# routeur3a.net
KiCad netlist of a schematic drawn in EAGLE
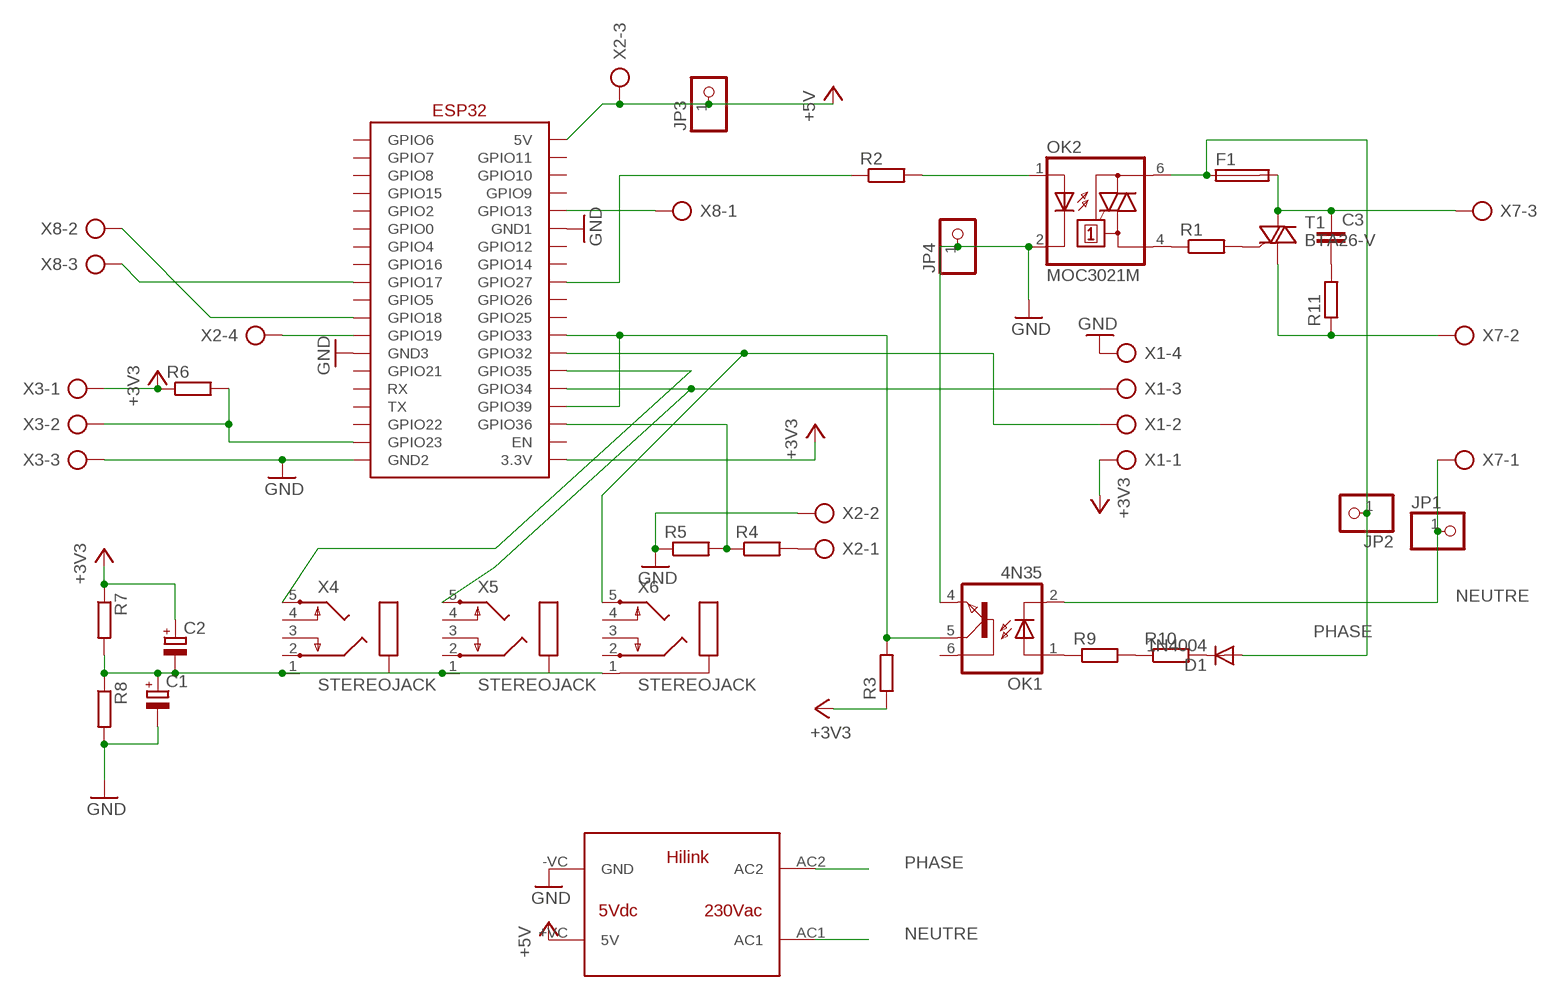
[diagram p0: schematic, sheet 1]

(export (version "E")
  (design (tool "Eeschema 10.0.6"))
  (components
    (comp (ref "C1")
      (value "CPOL-EUE5-8.5")
      (footprint "eagle-import:E5-8,5")
      (libsource (lib "eagle-import") (part "CPOL-EUE5-8.5"))
    )
    (comp (ref "C2")
      (value "CPOL-EUE5-8.5")
      (footprint "eagle-import:E5-8,5")
      (libsource (lib "eagle-import") (part "CPOL-EUE5-8.5"))
    )
    (comp (ref "C3")
      (value "C-EU150-072X183")
      (footprint "eagle-import:C150-072X183")
      (libsource (lib "eagle-import") (part "C-EU150-072X183"))
    )
    (comp (ref "D1")
      (value "1N4004")
      (footprint "eagle-import:DO41-10")
      (libsource (lib "eagle-import") (part "1N4004"))
    )
    (comp (ref "F1")
      (value "19560")
      (footprint "eagle-import:19560")
      (fields (field (name "MPN") "56000001009"))
      (libsource (lib "eagle-import") (part "19560"))
    )
    (comp (ref "JP1")
      (value "PINHD-1X1")
      (footprint "eagle-import:1X01")
      (libsource (lib "eagle-import") (part "PINHD-1X1"))
    )
    (comp (ref "JP2")
      (value "PINHD-1X1")
      (footprint "eagle-import:1X01")
      (libsource (lib "eagle-import") (part "PINHD-1X1"))
    )
    (comp (ref "JP3")
      (value "PINHD-1X1")
      (footprint "eagle-import:1X01")
      (libsource (lib "eagle-import") (part "PINHD-1X1"))
    )
    (comp (ref "JP4")
      (value "PINHD-1X1")
      (footprint "eagle-import:1X01")
      (libsource (lib "eagle-import") (part "PINHD-1X1"))
    )
    (comp (ref "OK1")
      (value "4N35")
      (footprint "eagle-import:DIL06")
      (fields (field (name "MF") "FAIRCHILD SEMICONDUCTOR"))
      (libsource (lib "eagle-import") (part "4N35"))
    )
    (comp (ref "OK2")
      (value "MOC3021M")
      (footprint "eagle-import:DIL06")
      (fields (field (name "MF") "FAIRCHILD SEMICONDUCTOR") (field (name "MPN") "MOC3021-M"))
      (libsource (lib "eagle-import") (part "MOC30M21"))
    )
    (comp (ref "R1")
      (value "R-EU_0207/10")
      (footprint "eagle-import:0207_10")
      (libsource (lib "eagle-import") (part "R-EU_0207/10"))
    )
    (comp (ref "R2")
      (value "R-EU_R1206")
      (footprint "eagle-import:R1206")
      (libsource (lib "eagle-import") (part "resistor_R-EU_R1206"))
    )
    (comp (ref "R3")
      (value "R-EU_R1206")
      (footprint "eagle-import:R1206")
      (libsource (lib "eagle-import") (part "resistor_R-EU_R1206"))
    )
    (comp (ref "R4")
      (value "R-EU_R1206")
      (footprint "eagle-import:R1206")
      (libsource (lib "eagle-import") (part "resistor_R-EU_R1206"))
    )
    (comp (ref "R5")
      (value "R-EU_R1206")
      (footprint "eagle-import:R1206")
      (libsource (lib "eagle-import") (part "resistor_R-EU_R1206"))
    )
    (comp (ref "R6")
      (value "R-EU_R1206")
      (footprint "eagle-import:R1206")
      (libsource (lib "eagle-import") (part "resistor_R-EU_R1206"))
    )
    (comp (ref "R7")
      (value "R-EU_R1206")
      (footprint "eagle-import:R1206")
      (libsource (lib "eagle-import") (part "resistor_R-EU_R1206"))
    )
    (comp (ref "R8")
      (value "R-EU_R1206")
      (footprint "eagle-import:R1206")
      (libsource (lib "eagle-import") (part "resistor_R-EU_R1206"))
    )
    (comp (ref "R9")
      (value "R-EU_0207/10")
      (footprint "eagle-import:0207_10")
      (libsource (lib "eagle-import") (part "R-EU_0207/10"))
    )
    (comp (ref "R10")
      (value "R-EU_0207/10")
      (footprint "eagle-import:0207_10")
      (libsource (lib "eagle-import") (part "R-EU_0207/10"))
    )
    (comp (ref "R11")
      (value "R-EU_0817/22")
      (footprint "eagle-import:P0817_22")
      (libsource (lib "eagle-import") (part "resistor_R-EU_0817/22"))
    )
    (comp (ref "T1")
      (value "BTA26-V")
      (footprint "eagle-import:TOP3S-1")
      (libsource (lib "eagle-import") (part "BTA26-V"))
    )
    (comp (ref "U$1")
      (value "WEMOSD1ESP32")
      (footprint "eagle-import:WEMOS-D1-MINI")
      (libsource (lib "eagle-import") (part "WEMOSD1ESP32"))
    )
    (comp (ref "U$2")
      (value "HILINK")
      (footprint "eagle-import:HILINK")
      (libsource (lib "eagle-import") (part "HILINK"))
    )
    (comp (ref "X1")
      (value "AK500/4")
      (footprint "eagle-import:AK500_4")
      (libsource (lib "eagle-import") (part "AK500/4"))
    )
    (comp (ref "X2")
      (value "AK500/4")
      (footprint "eagle-import:AK500_4")
      (libsource (lib "eagle-import") (part "AK500/4"))
    )
    (comp (ref "X3")
      (value "AK500/3")
      (footprint "eagle-import:AK500_3")
      (libsource (lib "eagle-import") (part "AK500/3"))
    )
    (comp (ref "X4")
      (value "STEREOJACK")
      (footprint "eagle-import:STX3100")
      (libsource (lib "eagle-import") (part "STEREOJACK"))
    )
    (comp (ref "X5")
      (value "STEREOJACK")
      (footprint "eagle-import:STX3100")
      (libsource (lib "eagle-import") (part "STEREOJACK"))
    )
    (comp (ref "X6")
      (value "STEREOJACK")
      (footprint "eagle-import:STX3100")
      (libsource (lib "eagle-import") (part "STEREOJACK"))
    )
    (comp (ref "X7")
      (value "AK500/3")
      (footprint "eagle-import:AK500_3")
      (libsource (lib "eagle-import") (part "AK500/3"))
    )
    (comp (ref "X8")
      (value "AK500/3")
      (footprint "eagle-import:AK500_3")
      (libsource (lib "eagle-import") (part "AK500/3"))
    )
  )
  (nets
    (net (code "1") (name "+3V3") (class "Default")
      (node (ref "C2") (pin "+") (pinfunction "+_+") (pintype "passive"))
      (node (ref "R3") (pin "1") (pinfunction "1_1") (pintype "passive"))
      (node (ref "R6") (pin "1") (pinfunction "1_1") (pintype "passive"))
      (node (ref "R7") (pin "1") (pinfunction "1_1") (pintype "passive"))
      (node (ref "U$1") (pin "3V3") (pinfunction "3.3V_3V3") (pintype "bidirectional"))
      (node (ref "X1") (pin "1") (pinfunction "KL_1") (pintype "passive"))
      (node (ref "X3") (pin "1") (pinfunction "KL_1") (pintype "passive"))
    )
    (net (code "2") (name "+5V") (class "Default")
      (node (ref "JP3") (pin "1") (pinfunction "1_1") (pintype "passive"))
      (node (ref "U$1") (pin "VCC") (pinfunction "5V_VCC") (pintype "bidirectional"))
      (node (ref "U$2") (pin "+VC") (pinfunction "5V_+VC") (pintype "bidirectional"))
      (node (ref "X2") (pin "3") (pinfunction "KL_3") (pintype "passive"))
    )
    (net (code "3") (name "/NEUTRE") (class "Default")
      (node (ref "JP1") (pin "1") (pinfunction "1_1") (pintype "passive"))
      (node (ref "OK1") (pin "2") (pinfunction "C_2") (pintype "passive"))
      (node (ref "U$2") (pin "AC1") (pinfunction "AC1_AC1") (pintype "bidirectional"))
      (node (ref "X7") (pin "1") (pinfunction "KL_1") (pintype "passive"))
    )
    (net (code "4") (name "/PHASE") (class "Default")
      (node (ref "D1") (pin "A") (pinfunction "A_A") (pintype "passive"))
      (node (ref "F1") (pin "1") (pinfunction "1_1") (pintype "passive"))
      (node (ref "JP2") (pin "1") (pinfunction "1_1") (pintype "passive"))
      (node (ref "OK2") (pin "6") (pinfunction "A2_6") (pintype "passive"))
      (node (ref "U$2") (pin "AC2") (pinfunction "AC2_AC2") (pintype "bidirectional"))
    )
    (net (code "5") (name "GND") (class "Default")
      (node (ref "C1") (pin "-") (pinfunction "-_-") (pintype "passive"))
      (node (ref "JP4") (pin "1") (pinfunction "1_1") (pintype "passive"))
      (node (ref "OK1") (pin "4") (pinfunction "EMI_4") (pintype "passive"))
      (node (ref "OK2") (pin "2") (pinfunction "C_2") (pintype "passive"))
      (node (ref "R5") (pin "1") (pinfunction "1_1") (pintype "passive"))
      (node (ref "R8") (pin "2") (pinfunction "2_2") (pintype "passive"))
      (node (ref "U$1") (pin "GND") (pinfunction "GND1_GND") (pintype "bidirectional"))
      (node (ref "U$1") (pin "GND2") (pinfunction "GND2_GND2") (pintype "bidirectional"))
      (node (ref "U$1") (pin "GND3") (pinfunction "GND3_GND3") (pintype "bidirectional"))
      (node (ref "U$2") (pin "-VC") (pinfunction "GND_-VC") (pintype "bidirectional"))
      (node (ref "X1") (pin "4") (pinfunction "KL_4") (pintype "passive"))
      (node (ref "X2") (pin "2") (pinfunction "KL_2") (pintype "passive"))
      (node (ref "X3") (pin "3") (pinfunction "KL_3") (pintype "passive"))
    )
    (net (code "6") (name "Net-(C1-Pad+)") (class "Default")
      (node (ref "C1") (pin "+") (pinfunction "+_+") (pintype "passive"))
      (node (ref "C2") (pin "-") (pinfunction "-_-") (pintype "passive"))
      (node (ref "R7") (pin "2") (pinfunction "2_2") (pintype "passive"))
      (node (ref "R8") (pin "1") (pinfunction "1_1") (pintype "passive"))
      (node (ref "X4") (pin "1") (pinfunction "1_1") (pintype "passive"))
      (node (ref "X5") (pin "1") (pinfunction "1_1") (pintype "passive"))
      (node (ref "X6") (pin "1") (pinfunction "1_1") (pintype "passive"))
    )
    (net (code "7") (name "Net-(C3-Pad2)") (class "Default")
      (node (ref "C3") (pin "2") (pinfunction "2_2") (pintype "passive"))
      (node (ref "R11") (pin "2") (pinfunction "2_2") (pintype "passive"))
    )
    (net (code "8") (name "Net-(D1-PadC)") (class "Default")
      (node (ref "D1") (pin "C") (pinfunction "C_C") (pintype "passive"))
      (node (ref "R10") (pin "2") (pinfunction "2_2") (pintype "passive"))
    )
    (net (code "9") (name "Net-(OK1-A)") (class "Default")
      (node (ref "OK1") (pin "1") (pinfunction "A_1") (pintype "passive"))
      (node (ref "R9") (pin "1") (pinfunction "1_1") (pintype "passive"))
    )
    (net (code "10") (name "Net-(OK1-COL)") (class "Default")
      (node (ref "OK1") (pin "5") (pinfunction "COL_5") (pintype "passive"))
      (node (ref "R3") (pin "2") (pinfunction "2_2") (pintype "passive"))
      (node (ref "U$1") (pin "33") (pinfunction "GPIO33_33") (pintype "bidirectional"))
      (node (ref "U$1") (pin "SUN") (pinfunction "GPIO39_SUN") (pintype "bidirectional"))
    )
    (net (code "11") (name "Net-(OK2-A)") (class "Default")
      (node (ref "OK2") (pin "1") (pinfunction "A_1") (pintype "passive"))
      (node (ref "R2") (pin "2") (pinfunction "2_2") (pintype "passive"))
    )
    (net (code "12") (name "Net-(OK2-A1)") (class "Default")
      (node (ref "OK2") (pin "4") (pinfunction "A1_4") (pintype "passive"))
      (node (ref "R1") (pin "1") (pinfunction "1_1") (pintype "passive"))
    )
    (net (code "13") (name "Net-(R1-Pad2)") (class "Default")
      (node (ref "R1") (pin "2") (pinfunction "2_2") (pintype "passive"))
      (node (ref "T1") (pin "G") (pinfunction "G_G") (pintype "passive"))
    )
    (net (code "14") (name "Net-(R10-Pad1)") (class "Default")
      (node (ref "R10") (pin "1") (pinfunction "1_1") (pintype "passive"))
      (node (ref "R9") (pin "2") (pinfunction "2_2") (pintype "passive"))
    )
    (net (code "15") (name "Net-(U$1-GPIO13)") (class "Default")
      (node (ref "U$1") (pin "TCK") (pinfunction "GPIO13_TCK") (pintype "bidirectional"))
      (node (ref "X8") (pin "1") (pinfunction "KL_1") (pintype "passive"))
    )
    (net (code "16") (name "Net-(U$1-GPIO17)") (class "Default")
      (node (ref "U$1") (pin "17") (pinfunction "GPIO17_17") (pintype "bidirectional"))
      (node (ref "X8") (pin "3") (pinfunction "KL_3") (pintype "passive"))
    )
    (net (code "17") (name "Net-(U$1-GPIO18)") (class "Default")
      (node (ref "U$1") (pin "18") (pinfunction "GPIO18_18") (pintype "bidirectional"))
      (node (ref "X8") (pin "2") (pinfunction "KL_2") (pintype "passive"))
    )
    (net (code "18") (name "Net-(U$1-GPIO19)") (class "Default")
      (node (ref "U$1") (pin "19") (pinfunction "GPIO19_19") (pintype "bidirectional"))
      (node (ref "X2") (pin "4") (pinfunction "KL_4") (pintype "passive"))
    )
    (net (code "19") (name "Net-(U$1-GPIO23)") (class "Default")
      (node (ref "R6") (pin "2") (pinfunction "2_2") (pintype "passive"))
      (node (ref "U$1") (pin "23") (pinfunction "GPIO23_23") (pintype "bidirectional"))
      (node (ref "X3") (pin "2") (pinfunction "KL_2") (pintype "passive"))
    )
    (net (code "20") (name "Net-(U$1-GPIO27)") (class "Default")
      (node (ref "R2") (pin "1") (pinfunction "1_1") (pintype "passive"))
      (node (ref "U$1") (pin "27") (pinfunction "GPIO27_27") (pintype "bidirectional"))
    )
    (net (code "21") (name "Net-(U$1-GPIO32)") (class "Default")
      (node (ref "U$1") (pin "32") (pinfunction "GPIO32_32") (pintype "bidirectional"))
      (node (ref "X1") (pin "2") (pinfunction "KL_2") (pintype "passive"))
      (node (ref "X6") (pin "5") (pinfunction "5_5") (pintype "passive"))
    )
    (net (code "22") (name "Net-(U$1-GPIO34)") (class "Default")
      (node (ref "U$1") (pin "34") (pinfunction "GPIO34_34") (pintype "bidirectional"))
      (node (ref "X1") (pin "3") (pinfunction "KL_3") (pintype "passive"))
      (node (ref "X5") (pin "5") (pinfunction "5_5") (pintype "passive"))
    )
    (net (code "23") (name "Net-(U$1-GPIO35)") (class "Default")
      (node (ref "U$1") (pin "35") (pinfunction "GPIO35_35") (pintype "bidirectional"))
      (node (ref "X4") (pin "5") (pinfunction "5_5") (pintype "passive"))
    )
    (net (code "24") (name "Net-(U$1-GPIO36)") (class "Default")
      (node (ref "R4") (pin "1") (pinfunction "1_1") (pintype "passive"))
      (node (ref "R5") (pin "2") (pinfunction "2_2") (pintype "passive"))
      (node (ref "U$1") (pin "SVP") (pinfunction "GPIO36_SVP") (pintype "bidirectional"))
    )
    (net (code "25") (name "Net-(X2A-KL)") (class "Default")
      (node (ref "R4") (pin "2") (pinfunction "2_2") (pintype "passive"))
      (node (ref "X2") (pin "1") (pinfunction "KL_1") (pintype "passive"))
    )
    (net (code "26") (name "Net-(X7B-KL)") (class "Default")
      (node (ref "R11") (pin "1") (pinfunction "1_1") (pintype "passive"))
      (node (ref "T1") (pin "A1") (pinfunction "A1_A1") (pintype "passive"))
      (node (ref "X7") (pin "2") (pinfunction "KL_2") (pintype "passive"))
    )
    (net (code "27") (name "Net-(X7C-KL)") (class "Default")
      (node (ref "C3") (pin "1") (pinfunction "1_1") (pintype "passive"))
      (node (ref "F1") (pin "2") (pinfunction "2_2") (pintype "passive"))
      (node (ref "T1") (pin "A2") (pinfunction "A2_A2") (pintype "passive"))
      (node (ref "X7") (pin "3") (pinfunction "KL_3") (pintype "passive"))
    )
    (net (code "28") (name "unconnected-(OK1-BAS-Pad6)") (class "Default")
      (node (ref "OK1") (pin "6") (pinfunction "BAS_6") (pintype "passive"))
    )
    (net (code "29") (name "unconnected-(U$1-EN-PadRST)") (class "Default")
      (node (ref "U$1") (pin "RST") (pinfunction "EN_RST") (pintype "bidirectional"))
    )
    (net (code "30") (name "unconnected-(U$1-GPIO0-Pad00)") (class "Default")
      (node (ref "U$1") (pin "00") (pinfunction "GPIO0_00") (pintype "bidirectional"))
    )
    (net (code "31") (name "unconnected-(U$1-GPIO2-Pad02)") (class "Default")
      (node (ref "U$1") (pin "02") (pinfunction "GPIO2_02") (pintype "bidirectional"))
    )
    (net (code "32") (name "unconnected-(U$1-GPIO4-Pad04)") (class "Default")
      (node (ref "U$1") (pin "04") (pinfunction "GPIO4_04") (pintype "bidirectional"))
    )
    (net (code "33") (name "unconnected-(U$1-GPIO5-Pad05)") (class "Default")
      (node (ref "U$1") (pin "05") (pinfunction "GPIO5_05") (pintype "bidirectional"))
    )
    (net (code "34") (name "unconnected-(U$1-GPIO6-PadCLK)") (class "Default")
      (node (ref "U$1") (pin "CLK") (pinfunction "GPIO6_CLK") (pintype "bidirectional"))
    )
    (net (code "35") (name "unconnected-(U$1-GPIO7-PadSDO)") (class "Default")
      (node (ref "U$1") (pin "SDO") (pinfunction "GPIO7_SDO") (pintype "bidirectional"))
    )
    (net (code "36") (name "unconnected-(U$1-GPIO8-PadSD1)") (class "Default")
      (node (ref "U$1") (pin "SD1") (pinfunction "GPIO8_SD1") (pintype "bidirectional"))
    )
    (net (code "37") (name "unconnected-(U$1-GPIO9-PadSD2)") (class "Default")
      (node (ref "U$1") (pin "SD2") (pinfunction "GPIO9_SD2") (pintype "bidirectional"))
    )
    (net (code "38") (name "unconnected-(U$1-GPIO10-PadSD3)") (class "Default")
      (node (ref "U$1") (pin "SD3") (pinfunction "GPIO10_SD3") (pintype "bidirectional"))
    )
    (net (code "39") (name "unconnected-(U$1-GPIO11-PadCMD)") (class "Default")
      (node (ref "U$1") (pin "CMD") (pinfunction "GPIO11_CMD") (pintype "bidirectional"))
    )
    (net (code "40") (name "unconnected-(U$1-GPIO12-PadTDI)") (class "Default")
      (node (ref "U$1") (pin "TDI") (pinfunction "GPIO12_TDI") (pintype "bidirectional"))
    )
    (net (code "41") (name "unconnected-(U$1-GPIO14-PadTMS)") (class "Default")
      (node (ref "U$1") (pin "TMS") (pinfunction "GPIO14_TMS") (pintype "bidirectional"))
    )
    (net (code "42") (name "unconnected-(U$1-GPIO15-PadTDO)") (class "Default")
      (node (ref "U$1") (pin "TDO") (pinfunction "GPIO15_TDO") (pintype "bidirectional"))
    )
    (net (code "43") (name "unconnected-(U$1-GPIO16-Pad16)") (class "Default")
      (node (ref "U$1") (pin "16") (pinfunction "GPIO16_16") (pintype "bidirectional"))
    )
    (net (code "44") (name "unconnected-(U$1-GPIO21-Pad21)") (class "Default")
      (node (ref "U$1") (pin "21") (pinfunction "GPIO21_21") (pintype "bidirectional"))
    )
    (net (code "45") (name "unconnected-(U$1-GPIO22-Pad22)") (class "Default")
      (node (ref "U$1") (pin "22") (pinfunction "GPIO22_22") (pintype "bidirectional"))
    )
    (net (code "46") (name "unconnected-(U$1-GPIO25-Pad25)") (class "Default")
      (node (ref "U$1") (pin "25") (pinfunction "GPIO25_25") (pintype "bidirectional"))
    )
    (net (code "47") (name "unconnected-(U$1-GPIO26-Pad26)") (class "Default")
      (node (ref "U$1") (pin "26") (pinfunction "GPIO26_26") (pintype "bidirectional"))
    )
    (net (code "48") (name "unconnected-(U$1-RX-PadRXD)") (class "Default")
      (node (ref "U$1") (pin "RXD") (pinfunction "RX_RXD") (pintype "bidirectional"))
    )
    (net (code "49") (name "unconnected-(U$1-TX-PadTXD)") (class "Default")
      (node (ref "U$1") (pin "TXD") (pinfunction "TX_TXD") (pintype "bidirectional"))
    )
    (net (code "50") (name "unconnected-(X4-Pad2)") (class "Default")
      (node (ref "X4") (pin "2") (pinfunction "2_2") (pintype "passive"))
    )
    (net (code "51") (name "unconnected-(X4-Pad3)") (class "Default")
      (node (ref "X4") (pin "3") (pinfunction "3_3") (pintype "passive"))
    )
    (net (code "52") (name "unconnected-(X4-Pad4)") (class "Default")
      (node (ref "X4") (pin "4") (pinfunction "4_4") (pintype "passive"))
    )
    (net (code "53") (name "unconnected-(X5-Pad2)") (class "Default")
      (node (ref "X5") (pin "2") (pinfunction "2_2") (pintype "passive"))
    )
    (net (code "54") (name "unconnected-(X5-Pad3)") (class "Default")
      (node (ref "X5") (pin "3") (pinfunction "3_3") (pintype "passive"))
    )
    (net (code "55") (name "unconnected-(X5-Pad4)") (class "Default")
      (node (ref "X5") (pin "4") (pinfunction "4_4") (pintype "passive"))
    )
    (net (code "56") (name "unconnected-(X6-Pad2)") (class "Default")
      (node (ref "X6") (pin "2") (pinfunction "2_2") (pintype "passive"))
    )
    (net (code "57") (name "unconnected-(X6-Pad3)") (class "Default")
      (node (ref "X6") (pin "3") (pinfunction "3_3") (pintype "passive"))
    )
    (net (code "58") (name "unconnected-(X6-Pad4)") (class "Default")
      (node (ref "X6") (pin "4") (pinfunction "4_4") (pintype "passive"))
    )
  )
)
